# WAirU_v1_1.net
KiCad netlist of a schematic drawn in EAGLE
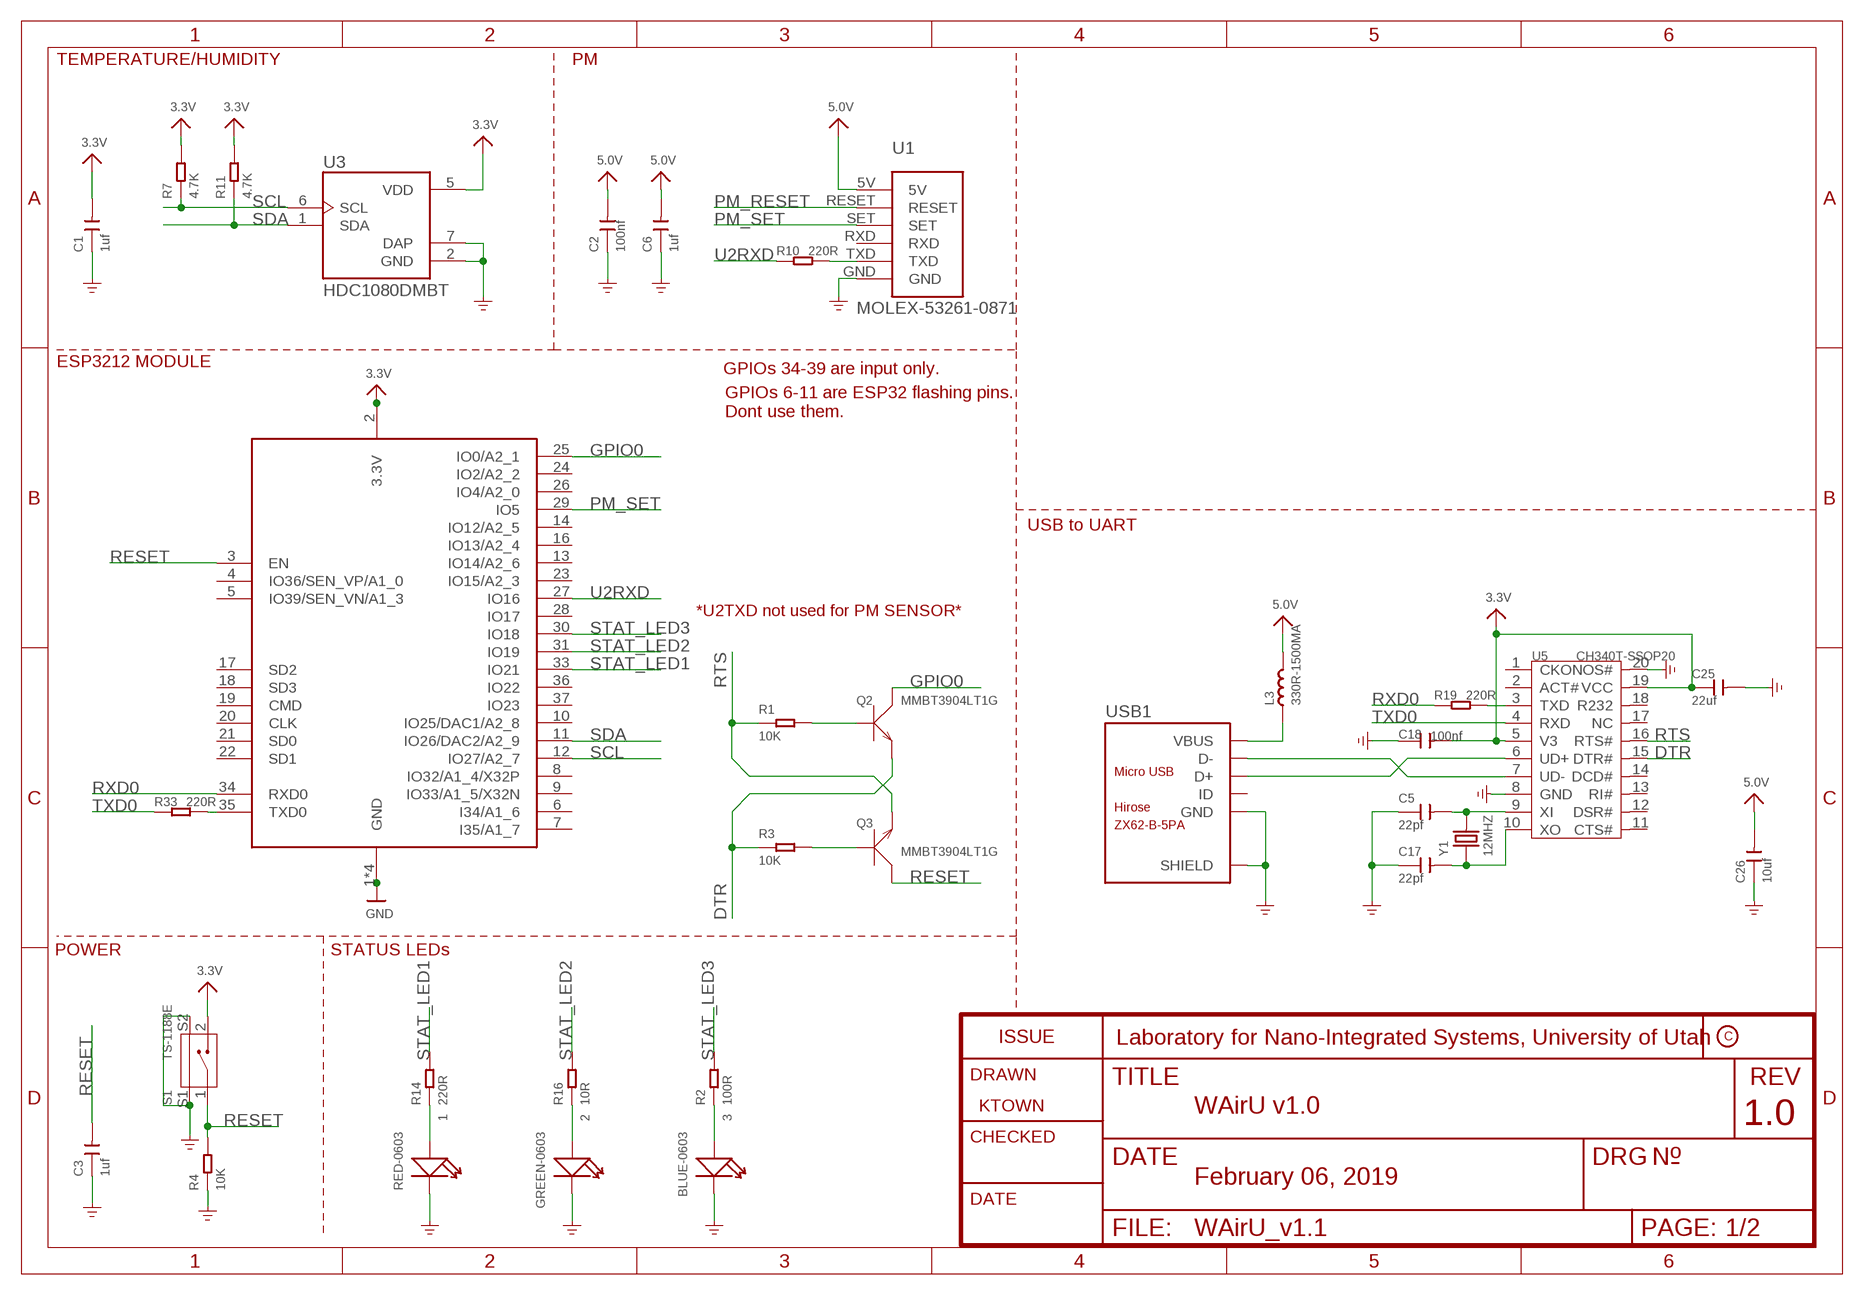
[diagram p0: schematic, sheet 1]
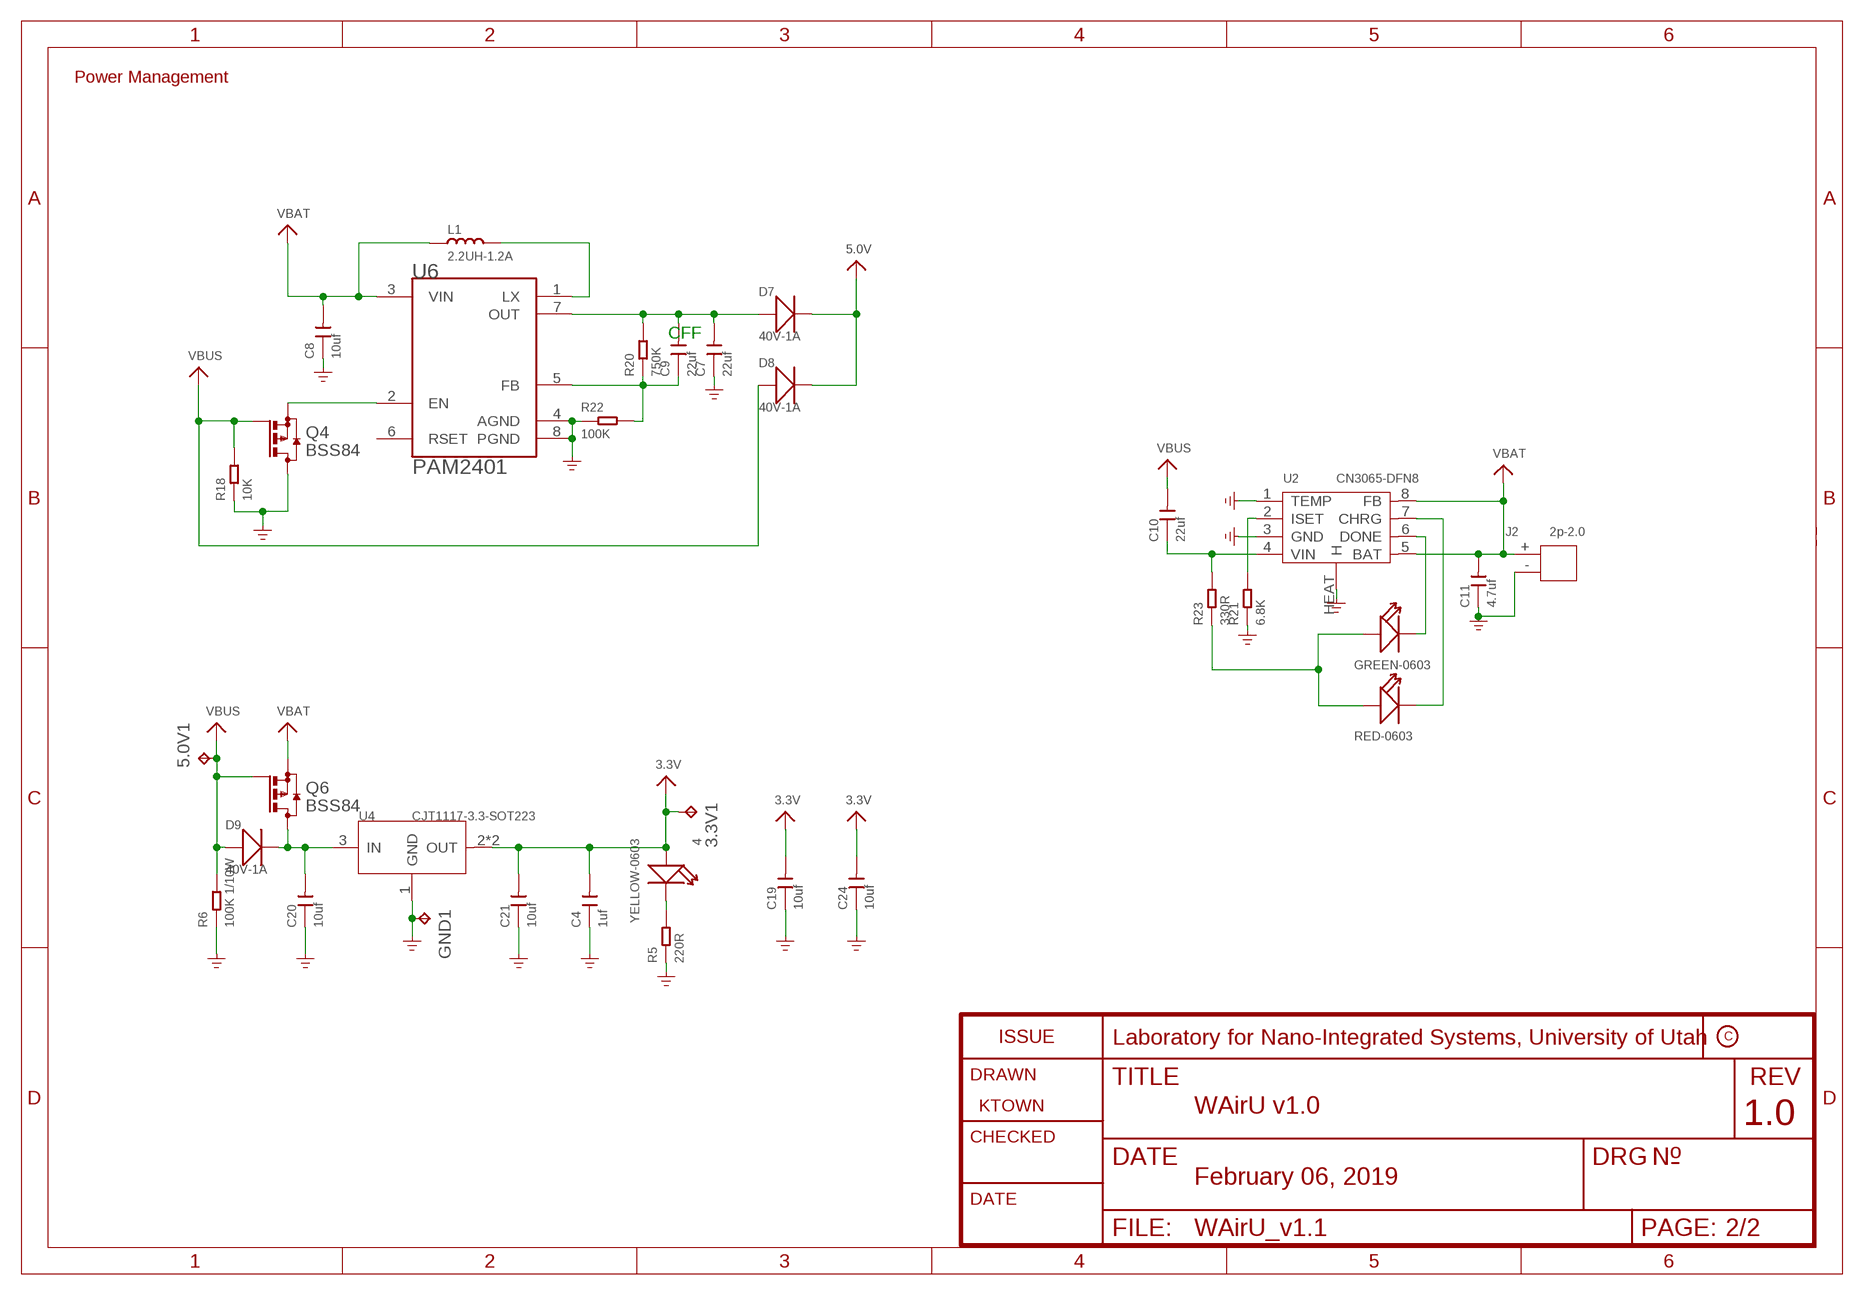
[diagram p1: schematic, sheet 2]

(export (version "E")
  (design (tool "Eeschema 10.0.6"))
  (components
    (comp (ref "1")
      (value "RED-0603")
      (footprint "eagle-import:LED-0603")
      (fields (field (name "MPN") "19-217-R6C-AL1M2VY-3T"))
      (libsource (lib "eagle-import") (part "LED-SMD-RED-DIFFUSED(0603)"))
    )
    (comp (ref "2")
      (value "GREEN-0603")
      (footprint "eagle-import:LED-0603")
      (fields (field (name "MPN") "19-217-G7C-AN1P2-3T"))
      (libsource (lib "eagle-import") (part "SMD-LED-CLEAR-GREEN(0603)"))
    )
    (comp (ref "3")
      (value "BLUE-0603")
      (footprint "eagle-import:LED-0603")
      (fields (field (name "MPN") "19-217-BHC-ZL1M2RY-3T"))
      (libsource (lib "eagle-import") (part "SMD-LED-CLEAR-BLUE(0603)"))
    )
    (comp (ref "C1")
      (value "1uf")
      (footprint "eagle-import:C0603")
      (fields (field (name "MPN") "CC0603KRX7R8BB105"))
      (libsource (lib "eagle-import") (part "CERAMIC-1UF-25V-10%-X7R(0603)"))
    )
    (comp (ref "C2")
      (value "100nf")
      (footprint "eagle-import:C0603")
      (fields (field (name "MPN") "CC0603KRX7R9BB104"))
      (libsource (lib "eagle-import") (part "CERAMIC-100NF-50V-10%-X7R(0603)"))
    )
    (comp (ref "C3")
      (value "1uf")
      (footprint "eagle-import:C0603")
      (fields (field (name "MPN") "CC0603KRX7R8BB105"))
      (libsource (lib "eagle-import") (part "CERAMIC-1UF-25V-10%-X7R(0603)"))
    )
    (comp (ref "C5")
      (value "22pf")
      (footprint "eagle-import:C0603")
      (fields (field (name "MPN") "CC0603JRNPO9BN220"))
      (libsource (lib "eagle-import") (part "CERAMIC-22PF-50V-5%-NPO(0603)"))
    )
    (comp (ref "C6")
      (value "1uf")
      (footprint "eagle-import:C0603")
      (fields (field (name "MPN") "CC0603KRX7R8BB105"))
      (libsource (lib "eagle-import") (part "CERAMIC-1UF-25V-10%-X7R(0603)"))
    )
    (comp (ref "C17")
      (value "22pf")
      (footprint "eagle-import:C0603")
      (fields (field (name "MPN") "CC0603JRNPO9BN220"))
      (libsource (lib "eagle-import") (part "CERAMIC-22PF-50V-5%-NPO(0603)"))
    )
    (comp (ref "C18")
      (value "100nf")
      (footprint "eagle-import:C0603")
      (fields (field (name "MPN") "CC0603KRX7R9BB104"))
      (libsource (lib "eagle-import") (part "CERAMIC-100NF-50V-10%-X7R(0603)"))
    )
    (comp (ref "C25")
      (value "22uf")
      (footprint "eagle-import:C0805")
      (fields (field (name "MPN") "CC0805MKX5R5BB226"))
      (libsource (lib "eagle-import") (part "CERAMIC-22UF-6.3V-20%-X5R(0805)"))
    )
    (comp (ref "C26")
      (value "10uf")
      (footprint "eagle-import:C0603")
      (fields (field (name "MPN") "CC0603KRX5R6BB106"))
      (libsource (lib "eagle-import") (part "Seeed-Capacitor_CERAMIC-10UF-10V-10%-X5R(0603)"))
    )
    (comp (ref "L3")
      (value "330R-1500MA")
      (footprint "eagle-import:L0805")
      (fields (field (name "MPN") "BLM21PG331SN1D"))
      (libsource (lib "eagle-import") (part "SMD-FERRITE-BEAD-330R-1500MA(0805)'0805'"))
    )
    (comp (ref "Q2")
      (value "MMBT3904LT1G")
      (footprint "eagle-import:SOT-23")
      (libsource (lib "eagle-import") (part "SMD-TRANSISTORS-NPN-40V-200MA-MMBT3904LT1G(SOT-23)"))
    )
    (comp (ref "Q3")
      (value "MMBT3904LT1G")
      (footprint "eagle-import:SOT-23")
      (libsource (lib "eagle-import") (part "SMD-TRANSISTORS-NPN-40V-200MA-MMBT3904LT1G(SOT-23)"))
    )
    (comp (ref "R1")
      (value "10K")
      (footprint "eagle-import:R0603")
      (fields (field (name "MPN") "RC0603FR-0710KL"))
      (libsource (lib "eagle-import") (part "SMD-RES-10K-1%-1/10W(0603)"))
    )
    (comp (ref "R2")
      (value "100R")
      (footprint "eagle-import:R0603")
      (fields (field (name "MPN") "RC0603JR-07100RL"))
      (libsource (lib "eagle-import") (part "SMD-RES-100R-5%-1/10W(0603)"))
    )
    (comp (ref "R3")
      (value "10K")
      (footprint "eagle-import:R0603")
      (fields (field (name "MPN") "RC0603FR-0710KL"))
      (libsource (lib "eagle-import") (part "SMD-RES-10K-1%-1/10W(0603)"))
    )
    (comp (ref "R4")
      (value "10K")
      (footprint "eagle-import:R0603")
      (fields (field (name "MPN") "RC0603FR-0710KL"))
      (libsource (lib "eagle-import") (part "SMD-RES-10K-1%-1/10W(0603)"))
    )
    (comp (ref "R7")
      (value "4.7K")
      (footprint "eagle-import:R0603")
      (fields (field (name "MPN") "RC0603JR-074K7L"))
      (libsource (lib "eagle-import") (part "SMD-RES-4.7K-5%-1/10W(0603)"))
    )
    (comp (ref "R10")
      (value "220R")
      (footprint "eagle-import:R0603")
      (fields (field (name "MPN") "RC0603JR-07220RL"))
      (libsource (lib "eagle-import") (part "SMD-RES-220R-5%-1/10W(0603)"))
    )
    (comp (ref "R11")
      (value "4.7K")
      (footprint "eagle-import:R0603")
      (fields (field (name "MPN") "RC0603JR-074K7L"))
      (libsource (lib "eagle-import") (part "SMD-RES-4.7K-5%-1/10W(0603)"))
    )
    (comp (ref "R14")
      (value "220R")
      (footprint "eagle-import:R0603")
      (fields (field (name "MPN") "RC0603JR-07220RL"))
      (libsource (lib "eagle-import") (part "SMD-RES-220R-5%-1/10W(0603)"))
    )
    (comp (ref "R16")
      (value "10R")
      (footprint "eagle-import:R0603")
      (fields (field (name "MPN") "RC0603JR-0710RL"))
      (libsource (lib "eagle-import") (part "SMD-RES-10R-5%-1/10W(0603)"))
    )
    (comp (ref "R19")
      (value "220R")
      (footprint "eagle-import:R0603")
      (fields (field (name "MPN") "RC0603JR-07220RL"))
      (libsource (lib "eagle-import") (part "SMD-RES-220R-5%-1/10W(0603)"))
    )
    (comp (ref "R33")
      (value "220R")
      (footprint "eagle-import:R0603")
      (fields (field (name "MPN") "RC0603JR-07220RL"))
      (libsource (lib "eagle-import") (part "SMD-RES-220R-5%-1/10W(0603)"))
    )
    (comp (ref "S1")
      (value "TS-1188E")
      (footprint "eagle-import:SW4-SMD-7.0X3.5X3.5MM-90D")
      (libsource (lib "eagle-import") (part "SMD-BUTTON(2+2P-7X3.5MM-90D)"))
    )
    (comp (ref "U1")
      (value "MOLEX-53261-0871")
      (footprint "eagle-import:MOLEX-53261-0871")
      (libsource (lib "eagle-import") (part "MOLEX-53261-0871"))
    )
    (comp (ref "U3")
      (value "HDC1080DMBT")
      (footprint "eagle-import:SON100P300X300X80-7N")
      (fields (field (name "DIGI-KEY_PART_NUMBER") "296-43864-1-ND") (field (name "MF") "Texas Instruments"))
      (libsource (lib "eagle-import") (part "HDC1080DMBT"))
    )
    (comp (ref "U5")
      (value "CH340T-SSOP20")
      (footprint "eagle-import:SSOP20-0.65-7.6X5.2MM")
      (fields (field (name "MPN") "CH340T"))
      (libsource (lib "eagle-import") (part "INTERFACE-CH340T(SSOP20)"))
    )
    (comp (ref "U7")
      (value "ESP32_WROOM32_SKINNY")
      (footprint "eagle-import:WROOM32_SKINNY")
      (libsource (lib "eagle-import") (part "ESP32_WROOM32_SKINNY"))
    )
    (comp (ref "USB1")
      (value "ZX62-B-5PA")
      (footprint "eagle-import:MICRO-USB5+6P-SMD-0.65-AB")
      (libsource (lib "eagle-import") (part "MICRO-USB-SMD(ZX62-B-5PA)"))
    )
    (comp (ref "Y1")
      (value "12MHZ")
      (footprint "eagle-import:X2-SMD-5.0X3.2X1.3MM")
      (fields (field (name "MPN") "5032/2P"))
      (libsource (lib "eagle-import") (part "SMD-CRYSTAL-12MHZ-20PF-20PPM-40R(2P-5.0X3.2MM)"))
    )
    (comp (ref "3.3V1")
      (value "TPTP20SQ")
      (footprint "eagle-import:TP20SQ")
      (libsource (lib "eagle-import") (part "TPTP20SQ"))
    )
    (comp (ref "4")
      (value "YELLOW-0603")
      (footprint "eagle-import:LED-0603")
      (fields (field (name "MPN") "19-217-Y5C-AM1N1VY-3T"))
      (libsource (lib "eagle-import") (part "SMD-LED-CLEAR-YELLOW(0603)"))
    )
    (comp (ref "5")
      (value "GREEN-0603")
      (footprint "eagle-import:LED-0603")
      (fields (field (name "MPN") "19-217-G7C-AN1P2-3T"))
      (libsource (lib "eagle-import") (part "SMD-LED-CLEAR-GREEN(0603)"))
    )
    (comp (ref "5.0V1")
      (value "TPTP20SQ")
      (footprint "eagle-import:TP20SQ")
      (libsource (lib "eagle-import") (part "TPTP20SQ"))
    )
    (comp (ref "6")
      (value "RED-0603")
      (footprint "eagle-import:LED-0603")
      (fields (field (name "MPN") "19-217-R6C-AL1M2VY-3T"))
      (libsource (lib "eagle-import") (part "LED-SMD-RED-DIFFUSED(0603)"))
    )
    (comp (ref "C4")
      (value "1uf")
      (footprint "eagle-import:C0603")
      (fields (field (name "MPN") "CC0603KRX7R8BB105"))
      (libsource (lib "eagle-import") (part "CERAMIC-1UF-25V-10%-X7R(0603)"))
    )
    (comp (ref "C7")
      (value "22uf")
      (footprint "eagle-import:C0603")
      (fields (field (name "MPN") "CC0603KRX5R6BB106"))
      (libsource (lib "eagle-import") (part "CERAMIC-10UF-10V-10%-X5R(0603)"))
    )
    (comp (ref "C8")
      (value "10uf")
      (footprint "eagle-import:C0603")
      (fields (field (name "MPN") "CC0603KRX5R6BB106"))
      (libsource (lib "eagle-import") (part "CERAMIC-10UF-10V-10%-X5R(0603)"))
    )
    (comp (ref "C9")
      (value "22uf")
      (footprint "eagle-import:C0603")
      (fields (field (name "MPN") "CC0603KRX5R6BB106"))
      (libsource (lib "eagle-import") (part "CERAMIC-10UF-10V-10%-X5R(0603)"))
    )
    (comp (ref "C10")
      (value "22uf")
      (footprint "eagle-import:C0603")
      (fields (field (name "MPN") "CC0603KRX5R6BB106"))
      (libsource (lib "eagle-import") (part "CERAMIC-10UF-10V-10%-X5R(0603)"))
    )
    (comp (ref "C11")
      (value "4.7uf")
      (footprint "eagle-import:C0603")
      (fields (field (name "MPN") "CC0603KRX5R6BB475"))
      (libsource (lib "eagle-import") (part "CERAMIC-4.7UF-10V-10%-X5R(0603)"))
    )
    (comp (ref "C19")
      (value "10uf")
      (footprint "eagle-import:C0603")
      (fields (field (name "MPN") "CC0603KRX5R6BB106"))
      (libsource (lib "eagle-import") (part "Seeed-Capacitor_CERAMIC-10UF-10V-10%-X5R(0603)"))
    )
    (comp (ref "C20")
      (value "10uf")
      (footprint "eagle-import:C0603")
      (fields (field (name "MPN") "CC0603KRX5R6BB106"))
      (libsource (lib "eagle-import") (part "Seeed-Capacitor_CERAMIC-10UF-10V-10%-X5R(0603)"))
    )
    (comp (ref "C21")
      (value "10uf")
      (footprint "eagle-import:C0603")
      (fields (field (name "MPN") "CC0603KRX5R6BB106"))
      (libsource (lib "eagle-import") (part "Seeed-Capacitor_CERAMIC-10UF-10V-10%-X5R(0603)"))
    )
    (comp (ref "C24")
      (value "10uf")
      (footprint "eagle-import:C0603")
      (fields (field (name "MPN") "CC0603KRX5R6BB106"))
      (libsource (lib "eagle-import") (part "Seeed-Capacitor_CERAMIC-10UF-10V-10%-X5R(0603)"))
    )
    (comp (ref "D7")
      (value "40V-1A")
      (footprint "eagle-import:DO-214AC")
      (fields (field (name "MPN") "1N5819"))
      (libsource (lib "eagle-import") (part "SMD-DIODE-SCHOTTKY-40V-1A(DO-214AC)"))
    )
    (comp (ref "D8")
      (value "40V-1A")
      (footprint "eagle-import:DO-214AC")
      (fields (field (name "MPN") "1N5819"))
      (libsource (lib "eagle-import") (part "SMD-DIODE-SCHOTTKY-40V-1A(DO-214AC)"))
    )
    (comp (ref "D9")
      (value "40V-1A")
      (footprint "eagle-import:DO-214AC")
      (fields (field (name "MPN") "1N5819"))
      (libsource (lib "eagle-import") (part "SMD-DIODE-SCHOTTKY-40V-1A(DO-214AC)"))
    )
    (comp (ref "GND1")
      (value "TPTP20SQ")
      (footprint "eagle-import:TP20SQ")
      (libsource (lib "eagle-import") (part "TPTP20SQ"))
    )
    (comp (ref "J2")
      (value "2p-2.0")
      (footprint "eagle-import:H2-2.0-6X4.5MM")
      (libsource (lib "eagle-import") (part "DIP-JST-2P-2.0"))
    )
    (comp (ref "L1")
      (value "2.2UH-1.2A")
      (footprint "eagle-import:L0805")
      (fields (field (name "MPN") "LQM2MPN2R2MG0"))
      (libsource (lib "eagle-import") (part "SMD-INDUCTOR-2.2UH-20%-1.2A(0805)"))
    )
    (comp (ref "Q4")
      (value "BSS84")
      (footprint "eagle-import:SOT23")
      (fields (field (name "MF") "MICROSS/On Semiconductor"))
      (libsource (lib "eagle-import") (part "BSS84"))
    )
    (comp (ref "Q6")
      (value "BSS84")
      (footprint "eagle-import:SOT23")
      (fields (field (name "MF") "MICROSS/On Semiconductor"))
      (libsource (lib "eagle-import") (part "BSS84"))
    )
    (comp (ref "R5")
      (value "220R")
      (footprint "eagle-import:R0603")
      (fields (field (name "MPN") "RC0603JR-07220RL"))
      (libsource (lib "eagle-import") (part "SMD-RES-220R-5%-1/10W(0603)"))
    )
    (comp (ref "R6")
      (value "100K 1/10W")
      (footprint "eagle-import:R0603")
      (fields (field (name "MPN") "RC0603JR-07100KL"))
      (libsource (lib "eagle-import") (part "Seeed-Resistor_SMD-RES-100K-5%-1/10W(0603)"))
    )
    (comp (ref "R18")
      (value "10K")
      (footprint "eagle-import:R0603")
      (fields (field (name "MPN") "RC0603FR-0710KL"))
      (libsource (lib "eagle-import") (part "SMD-RES-10K-1%-1/10W(0603)"))
    )
    (comp (ref "R20")
      (value "750K")
      (footprint "eagle-import:R0603")
      (fields (field (name "MPN") "RC0603JR-07100KL"))
      (libsource (lib "eagle-import") (part "SMD-RES-100K-5%-1/10W(0603)"))
    )
    (comp (ref "R21")
      (value "6.8K")
      (footprint "eagle-import:R0603")
      (fields (field (name "MPN") "RC0805JR-07220KL"))
      (libsource (lib "eagle-import") (part "SMD-RES-6.8K-1%-1/10W(0603)"))
    )
    (comp (ref "R22")
      (value "100K")
      (footprint "eagle-import:R0603")
      (fields (field (name "MPN") "RC0603JR-07100KL"))
      (libsource (lib "eagle-import") (part "SMD-RES-100K-5%-1/10W(0603)"))
    )
    (comp (ref "R23")
      (value "330R")
      (footprint "eagle-import:R0603")
      (fields (field (name "MPN") "RC0603FR-07330RL"))
      (libsource (lib "eagle-import") (part "SMD-RES-330R-1%-1/10W(0603)"))
    )
    (comp (ref "U2")
      (value "CN3065-DFN8")
      (footprint "eagle-import:DFN8G-0.5-3X3MM")
      (fields (field (name "MPN") "CN3065"))
      (libsource (lib "eagle-import") (part "PMIC-CN3065(DFN8)"))
    )
    (comp (ref "U4")
      (value "CJT1117-3.3-SOT223")
      (footprint "eagle-import:SOT-223")
      (fields (field (name "MPN") "CJT1117-3.3"))
      (libsource (lib "eagle-import") (part "PMIC-CJT1117-3.3(SOT223)"))
    )
    (comp (ref "U6")
      (value "PAM2401")
      (footprint "eagle-import:MSOP-8")
      (libsource (lib "eagle-import") (part "PAM2401"))
    )
  )
  (nets
    (net (code "1") (name "3.3V") (class "Default")
      (node (ref "3.3V1") (pin "TP") (pinfunction "TP_TP") (pintype "input"))
      (node (ref "4") (pin "+") (pinfunction "+_+") (pintype "passive"))
      (node (ref "C1") (pin "2") (pinfunction "2_2") (pintype "passive"))
      (node (ref "C18") (pin "2") (pinfunction "2_2") (pintype "passive"))
      (node (ref "C19") (pin "2") (pinfunction "2_2") (pintype "passive"))
      (node (ref "C21") (pin "2") (pinfunction "2_2") (pintype "passive"))
      (node (ref "C24") (pin "2") (pinfunction "2_2") (pintype "passive"))
      (node (ref "C25") (pin "1") (pinfunction "1_1") (pintype "passive"))
      (node (ref "C4") (pin "2") (pinfunction "2_2") (pintype "passive"))
      (node (ref "R11") (pin "2") (pinfunction "2_2") (pintype "passive"))
      (node (ref "R7") (pin "2") (pinfunction "2_2") (pintype "passive"))
      (node (ref "S1") (pin "2") (pinfunction "2_2") (pintype "bidirectional"))
      (node (ref "U3") (pin "5") (pinfunction "VDD_5") (pintype "power_in"))
      (node (ref "U4") (pin "2") (pinfunction "OUT_2") (pintype "bidirectional"))
      (node (ref "U4") (pin "TER") (pinfunction "OUT_TER") (pintype "bidirectional"))
      (node (ref "U5") (pin "19") (pinfunction "VCC_19") (pintype "power_in"))
      (node (ref "U5") (pin "5") (pinfunction "V3_5") (pintype "power_in"))
      (node (ref "U7") (pin "2") (pinfunction "3.3V_2") (pintype "passive"))
    )
    (net (code "2") (name "5.0V") (class "Default")
      (node (ref "C2") (pin "2") (pinfunction "2_2") (pintype "passive"))
      (node (ref "C26") (pin "2") (pinfunction "2_2") (pintype "passive"))
      (node (ref "C6") (pin "2") (pinfunction "2_2") (pintype "passive"))
      (node (ref "D7") (pin "2") (pinfunction "-_2") (pintype "passive"))
      (node (ref "D8") (pin "2") (pinfunction "-_2") (pintype "passive"))
      (node (ref "L3") (pin "2") (pinfunction "2_2") (pintype "passive"))
      (node (ref "U1") (pin "5V") (pinfunction "5V_5V") (pintype "bidirectional"))
    )
    (net (code "3") (name "DTR") (class "Default")
      (node (ref "Q2") (pin "2") (pinfunction "E_2") (pintype "passive"))
      (node (ref "R3") (pin "1") (pinfunction "1_1") (pintype "passive"))
      (node (ref "U5") (pin "15") (pinfunction "DTR#_15") (pintype "output"))
    )
    (net (code "4") (name "GND") (class "Default")
      (node (ref "1") (pin "-") (pinfunction "-_-") (pintype "passive"))
      (node (ref "2") (pin "-") (pinfunction "-_-") (pintype "passive"))
      (node (ref "3") (pin "-") (pinfunction "-_-") (pintype "passive"))
      (node (ref "C1") (pin "1") (pinfunction "1_1") (pintype "passive"))
      (node (ref "C11") (pin "1") (pinfunction "1_1") (pintype "passive"))
      (node (ref "C17") (pin "1") (pinfunction "1_1") (pintype "passive"))
      (node (ref "C18") (pin "1") (pinfunction "1_1") (pintype "passive"))
      (node (ref "C19") (pin "1") (pinfunction "1_1") (pintype "passive"))
      (node (ref "C2") (pin "1") (pinfunction "1_1") (pintype "passive"))
      (node (ref "C20") (pin "1") (pinfunction "1_1") (pintype "passive"))
      (node (ref "C21") (pin "1") (pinfunction "1_1") (pintype "passive"))
      (node (ref "C24") (pin "1") (pinfunction "1_1") (pintype "passive"))
      (node (ref "C25") (pin "2") (pinfunction "2_2") (pintype "passive"))
      (node (ref "C26") (pin "1") (pinfunction "1_1") (pintype "passive"))
      (node (ref "C3") (pin "1") (pinfunction "1_1") (pintype "passive"))
      (node (ref "C4") (pin "1") (pinfunction "1_1") (pintype "passive"))
      (node (ref "C5") (pin "1") (pinfunction "1_1") (pintype "passive"))
      (node (ref "C6") (pin "1") (pinfunction "1_1") (pintype "passive"))
      (node (ref "C7") (pin "1") (pinfunction "1_1") (pintype "passive"))
      (node (ref "C8") (pin "1") (pinfunction "1_1") (pintype "passive"))
      (node (ref "GND1") (pin "TP") (pinfunction "TP_TP") (pintype "input"))
      (node (ref "J2") (pin "-") (pinfunction "P$2_-") (pintype "bidirectional"))
      (node (ref "Q4") (pin "3") (pinfunction "D_3") (pintype "passive"))
      (node (ref "R18") (pin "1") (pinfunction "1_1") (pintype "passive"))
      (node (ref "R21") (pin "1") (pinfunction "1_1") (pintype "passive"))
      (node (ref "R22") (pin "1") (pinfunction "1_1") (pintype "passive"))
      (node (ref "R4") (pin "1") (pinfunction "1_1") (pintype "passive"))
      (node (ref "R5") (pin "1") (pinfunction "1_1") (pintype "passive"))
      (node (ref "R6") (pin "1") (pinfunction "1_1") (pintype "passive"))
      (node (ref "S1") (pin "S1") (pinfunction "S1_S1") (pintype "bidirectional"))
      (node (ref "S1") (pin "S2") (pinfunction "S2_S2") (pintype "bidirectional"))
      (node (ref "U1") (pin "GND") (pinfunction "GND_GND") (pintype "bidirectional"))
      (node (ref "U2") (pin "1") (pinfunction "TEMP_1") (pintype "input"))
      (node (ref "U2") (pin "3") (pinfunction "GND_3") (pintype "power_in"))
      (node (ref "U2") (pin "HEAT") (pinfunction "H_HEAT") (pintype "bidirectional"))
      (node (ref "U3") (pin "2") (pinfunction "GND_2") (pintype "power_in"))
      (node (ref "U3") (pin "7") (pinfunction "DAP_7") (pintype "power_in"))
      (node (ref "U4") (pin "1") (pinfunction "GND_1") (pintype "bidirectional"))
      (node (ref "U5") (pin "20") (pinfunction "NOS#_20") (pintype "power_in"))
      (node (ref "U5") (pin "8") (pinfunction "GND_8") (pintype "power_in"))
      (node (ref "U6") (pin "4") (pinfunction "AGND_4") (pintype "bidirectional"))
      (node (ref "U6") (pin "8") (pinfunction "PGND_8") (pintype "bidirectional"))
      (node (ref "U7") (pin "1") (pinfunction "GND_1") (pintype "passive"))
      (node (ref "U7") (pin "15") (pinfunction "GND_15") (pintype "passive"))
      (node (ref "U7") (pin "38") (pinfunction "GND_38") (pintype "passive"))
      (node (ref "U7") (pin "P$1") (pinfunction "GND_P$1") (pintype "passive"))
      (node (ref "USB1") (pin "5") (pinfunction "GND_5") (pintype "power_in"))
      (node (ref "USB1") (pin "P1") (pinfunction "SHIELD_P1") (pintype "power_in"))
      (node (ref "USB1") (pin "P2") (pinfunction "SHIELD_P2") (pintype "power_in"))
      (node (ref "USB1") (pin "P3_1") (pinfunction "SHIELD_P3_1") (pintype "power_in"))
      (node (ref "USB1") (pin "P3_2") (pinfunction "SHIELD_P3_2") (pintype "power_in"))
      (node (ref "USB1") (pin "P3_3") (pinfunction "SHIELD_P3_3") (pintype "power_in"))
      (node (ref "USB1") (pin "P4_1") (pinfunction "SHIELD_P4_1") (pintype "power_in"))
      (node (ref "USB1") (pin "P4_2") (pinfunction "SHIELD_P4_2") (pintype "power_in"))
      (node (ref "USB1") (pin "P4_3") (pinfunction "SHIELD_P4_3") (pintype "power_in"))
      (node (ref "USB1") (pin "P5") (pinfunction "SHIELD_P5") (pintype "power_in"))
      (node (ref "USB1") (pin "P6") (pinfunction "SHIELD_P6") (pintype "power_in"))
    )
    (net (code "5") (name "GPIO0") (class "Default")
      (node (ref "Q2") (pin "3") (pinfunction "C_3") (pintype "passive"))
      (node (ref "U7") (pin "25") (pinfunction "IO0/A2_1_25") (pintype "bidirectional"))
    )
    (net (code "6") (name "Net-(1-Pad+)") (class "Default")
      (node (ref "1") (pin "+") (pinfunction "+_+") (pintype "passive"))
      (node (ref "R14") (pin "1") (pinfunction "1_1") (pintype "passive"))
    )
    (net (code "7") (name "Net-(2-Pad+)") (class "Default")
      (node (ref "2") (pin "+") (pinfunction "+_+") (pintype "passive"))
      (node (ref "R16") (pin "1") (pinfunction "1_1") (pintype "passive"))
    )
    (net (code "8") (name "Net-(3-Pad+)") (class "Default")
      (node (ref "3") (pin "+") (pinfunction "+_+") (pintype "passive"))
      (node (ref "R2") (pin "1") (pinfunction "1_1") (pintype "passive"))
    )
    (net (code "9") (name "Net-(4-Pad-)") (class "Default")
      (node (ref "4") (pin "-") (pinfunction "-_-") (pintype "passive"))
      (node (ref "R5") (pin "2") (pinfunction "2_2") (pintype "passive"))
    )
    (net (code "10") (name "Net-(5-Pad+)") (class "Default")
      (node (ref "5") (pin "+") (pinfunction "+_+") (pintype "passive"))
      (node (ref "6") (pin "+") (pinfunction "+_+") (pintype "passive"))
      (node (ref "R23") (pin "1") (pinfunction "1_1") (pintype "passive"))
    )
    (net (code "11") (name "Net-(D7-+)") (class "Default")
      (node (ref "C7") (pin "2") (pinfunction "2_2") (pintype "passive"))
      (node (ref "C9") (pin "2") (pinfunction "2_2") (pintype "passive"))
      (node (ref "D7") (pin "1") (pinfunction "+_1") (pintype "passive"))
      (node (ref "R20") (pin "2") (pinfunction "2_2") (pintype "passive"))
      (node (ref "U6") (pin "7") (pinfunction "OUT_7") (pintype "bidirectional"))
    )
    (net (code "12") (name "Net-(D9--)") (class "Default")
      (node (ref "C20") (pin "2") (pinfunction "2_2") (pintype "passive"))
      (node (ref "D9") (pin "2") (pinfunction "-_2") (pintype "passive"))
      (node (ref "Q6") (pin "3") (pinfunction "D_3") (pintype "passive"))
      (node (ref "U4") (pin "3") (pinfunction "IN_3") (pintype "bidirectional"))
    )
    (net (code "13") (name "Net-(Q2-B)") (class "Default")
      (node (ref "Q2") (pin "1") (pinfunction "B_1") (pintype "passive"))
      (node (ref "R1") (pin "2") (pinfunction "2_2") (pintype "passive"))
    )
    (net (code "14") (name "Net-(Q3-B)") (class "Default")
      (node (ref "Q3") (pin "1") (pinfunction "B_1") (pintype "passive"))
      (node (ref "R3") (pin "2") (pinfunction "2_2") (pintype "passive"))
    )
    (net (code "15") (name "Net-(Q4-S)") (class "Default")
      (node (ref "Q4") (pin "2") (pinfunction "S_2") (pintype "passive"))
      (node (ref "U6") (pin "2") (pinfunction "EN_2") (pintype "bidirectional"))
    )
    (net (code "16") (name "Net-(R10-Pad2)") (class "Default")
      (node (ref "R10") (pin "2") (pinfunction "2_2") (pintype "passive"))
      (node (ref "U1") (pin "TXD") (pinfunction "TXD_TXD") (pintype "bidirectional"))
    )
    (net (code "17") (name "Net-(U2-CHRG)") (class "Default")
      (node (ref "6") (pin "-") (pinfunction "-_-") (pintype "passive"))
      (node (ref "U2") (pin "7") (pinfunction "CHRG_7") (pintype "bidirectional"))
    )
    (net (code "18") (name "Net-(U2-DONE)") (class "Default")
      (node (ref "5") (pin "-") (pinfunction "-_-") (pintype "passive"))
      (node (ref "U2") (pin "6") (pinfunction "DONE_6") (pintype "bidirectional"))
    )
    (net (code "19") (name "Net-(U2-ISET)") (class "Default")
      (node (ref "R21") (pin "2") (pinfunction "2_2") (pintype "passive"))
      (node (ref "U2") (pin "2") (pinfunction "ISET_2") (pintype "bidirectional"))
    )
    (net (code "20") (name "Net-(U2-VIN)") (class "Default")
      (node (ref "C10") (pin "1") (pinfunction "1_1") (pintype "passive"))
      (node (ref "R23") (pin "2") (pinfunction "2_2") (pintype "passive"))
      (node (ref "U2") (pin "4") (pinfunction "VIN_4") (pintype "input"))
    )
    (net (code "21") (name "Net-(U5-TXD)") (class "Default")
      (node (ref "R19") (pin "2") (pinfunction "2_2") (pintype "passive"))
      (node (ref "U5") (pin "3") (pinfunction "TXD_3") (pintype "output"))
    )
    (net (code "22") (name "Net-(U5-UD+)") (class "Default")
      (node (ref "U5") (pin "6") (pinfunction "UD+_6") (pintype "bidirectional"))
      (node (ref "USB1") (pin "3") (pinfunction "D+_3") (pintype "bidirectional"))
    )
    (net (code "23") (name "Net-(U5-UD-)") (class "Default")
      (node (ref "U5") (pin "7") (pinfunction "UD-_7") (pintype "bidirectional"))
      (node (ref "USB1") (pin "2") (pinfunction "D-_2") (pintype "bidirectional"))
    )
    (net (code "24") (name "Net-(U5-XI)") (class "Default")
      (node (ref "C5") (pin "2") (pinfunction "2_2") (pintype "passive"))
      (node (ref "U5") (pin "9") (pinfunction "XI_9") (pintype "input"))
      (node (ref "Y1") (pin "2") (pinfunction "2_2") (pintype "passive"))
    )
    (net (code "25") (name "Net-(U5-XO)") (class "Default")
      (node (ref "C17") (pin "2") (pinfunction "2_2") (pintype "passive"))
      (node (ref "U5") (pin "10") (pinfunction "XO_10") (pintype "output"))
      (node (ref "Y1") (pin "1") (pinfunction "1_1") (pintype "passive"))
    )
    (net (code "26") (name "Net-(U6-FB)") (class "Default")
      (node (ref "C9") (pin "1") (pinfunction "1_1") (pintype "passive"))
      (node (ref "R20") (pin "1") (pinfunction "1_1") (pintype "passive"))
      (node (ref "R22") (pin "2") (pinfunction "2_2") (pintype "passive"))
      (node (ref "U6") (pin "5") (pinfunction "FB_5") (pintype "bidirectional"))
    )
    (net (code "27") (name "Net-(U6-LX)") (class "Default")
      (node (ref "L1") (pin "2") (pinfunction "2_2") (pintype "passive"))
      (node (ref "U6") (pin "1") (pinfunction "LX_1") (pintype "bidirectional"))
    )
    (net (code "28") (name "Net-(U7-TXD0)") (class "Default")
      (node (ref "R33") (pin "2") (pinfunction "2_2") (pintype "passive"))
      (node (ref "U7") (pin "35") (pinfunction "TXD0_35") (pintype "output"))
    )
    (net (code "29") (name "PM_RESET") (class "Default")
      (node (ref "U1") (pin "RESET") (pinfunction "RESET_RESET") (pintype "bidirectional"))
    )
    (net (code "30") (name "PM_SET") (class "Default")
      (node (ref "U1") (pin "SET") (pinfunction "SET_SET") (pintype "bidirectional"))
      (node (ref "U7") (pin "29") (pinfunction "IO5_29") (pintype "bidirectional"))
    )
    (net (code "31") (name "RESET") (class "Default")
      (node (ref "C3") (pin "2") (pinfunction "2_2") (pintype "passive"))
      (node (ref "Q3") (pin "3") (pinfunction "C_3") (pintype "passive"))
      (node (ref "R4") (pin "2") (pinfunction "2_2") (pintype "passive"))
      (node (ref "S1") (pin "1") (pinfunction "1_1") (pintype "bidirectional"))
      (node (ref "U7") (pin "3") (pinfunction "EN_3") (pintype "input"))
    )
    (net (code "32") (name "RTS") (class "Default")
      (node (ref "Q3") (pin "2") (pinfunction "E_2") (pintype "passive"))
      (node (ref "R1") (pin "1") (pinfunction "1_1") (pintype "passive"))
      (node (ref "U5") (pin "16") (pinfunction "RTS#_16") (pintype "output"))
    )
    (net (code "33") (name "RXD0") (class "Default")
      (node (ref "R19") (pin "1") (pinfunction "1_1") (pintype "passive"))
      (node (ref "U7") (pin "34") (pinfunction "RXD0_34") (pintype "input"))
    )
    (net (code "34") (name "SCL") (class "Default")
      (node (ref "R7") (pin "1") (pinfunction "1_1") (pintype "passive"))
      (node (ref "U3") (pin "6") (pinfunction "SCL_6") (pintype "input"))
      (node (ref "U7") (pin "12") (pinfunction "IO27/A2_7_12") (pintype "bidirectional"))
    )
    (net (code "35") (name "SDA") (class "Default")
      (node (ref "R11") (pin "1") (pinfunction "1_1") (pintype "passive"))
      (node (ref "U3") (pin "1") (pinfunction "SDA_1") (pintype "bidirectional"))
      (node (ref "U7") (pin "11") (pinfunction "IO26/DAC2/A2_9_11") (pintype "bidirectional"))
    )
    (net (code "36") (name "STAT_LED1") (class "Default")
      (node (ref "R14") (pin "2") (pinfunction "2_2") (pintype "passive"))
      (node (ref "U7") (pin "33") (pinfunction "IO21_33") (pintype "bidirectional"))
    )
    (net (code "37") (name "STAT_LED2") (class "Default")
      (node (ref "R16") (pin "2") (pinfunction "2_2") (pintype "passive"))
      (node (ref "U7") (pin "31") (pinfunction "IO19_31") (pintype "bidirectional"))
    )
    (net (code "38") (name "STAT_LED3") (class "Default")
      (node (ref "R2") (pin "2") (pinfunction "2_2") (pintype "passive"))
      (node (ref "U7") (pin "30") (pinfunction "IO18_30") (pintype "bidirectional"))
    )
    (net (code "39") (name "TXD0") (class "Default")
      (node (ref "R33") (pin "1") (pinfunction "1_1") (pintype "passive"))
      (node (ref "U5") (pin "4") (pinfunction "RXD_4") (pintype "input"))
    )
    (net (code "40") (name "U2RXD") (class "Default")
      (node (ref "R10") (pin "1") (pinfunction "1_1") (pintype "passive"))
      (node (ref "U7") (pin "27") (pinfunction "IO16_27") (pintype "bidirectional"))
    )
    (net (code "41") (name "VBAT") (class "Default")
      (node (ref "C11") (pin "2") (pinfunction "2_2") (pintype "passive"))
      (node (ref "C8") (pin "2") (pinfunction "2_2") (pintype "passive"))
      (node (ref "J2") (pin "+") (pinfunction "P$1_+") (pintype "bidirectional"))
      (node (ref "L1") (pin "1") (pinfunction "1_1") (pintype "passive"))
      (node (ref "Q6") (pin "2") (pinfunction "S_2") (pintype "passive"))
      (node (ref "U2") (pin "5") (pinfunction "BAT_5") (pintype "bidirectional"))
      (node (ref "U2") (pin "8") (pinfunction "FB_8") (pintype "input"))
      (node (ref "U6") (pin "3") (pinfunction "VIN_3") (pintype "bidirectional"))
    )
    (net (code "42") (name "VBUS") (class "Default")
      (node (ref "5.0V1") (pin "TP") (pinfunction "TP_TP") (pintype "input"))
      (node (ref "C10") (pin "2") (pinfunction "2_2") (pintype "passive"))
      (node (ref "D8") (pin "1") (pinfunction "+_1") (pintype "passive"))
      (node (ref "D9") (pin "1") (pinfunction "+_1") (pintype "passive"))
      (node (ref "L3") (pin "1") (pinfunction "1_1") (pintype "passive"))
      (node (ref "Q4") (pin "1") (pinfunction "G_1") (pintype "passive"))
      (node (ref "Q6") (pin "1") (pinfunction "G_1") (pintype "passive"))
      (node (ref "R18") (pin "2") (pinfunction "2_2") (pintype "passive"))
      (node (ref "R6") (pin "2") (pinfunction "2_2") (pintype "passive"))
      (node (ref "USB1") (pin "1") (pinfunction "VBUS_1") (pintype "power_in"))
    )
    (net (code "43") (name "unconnected-(U1-PadRXD)") (class "Default")
      (node (ref "U1") (pin "RXD") (pinfunction "RXD_RXD") (pintype "bidirectional"))
    )
    (net (code "44") (name "unconnected-(U5-ACT#-Pad2)") (class "Default")
      (node (ref "U5") (pin "2") (pinfunction "ACT#_2") (pintype "output"))
    )
    (net (code "45") (name "unconnected-(U5-CKO-Pad1)") (class "Default")
      (node (ref "U5") (pin "1") (pinfunction "CKO_1") (pintype "output"))
    )
    (net (code "46") (name "unconnected-(U5-CTS#-Pad11)") (class "Default")
      (node (ref "U5") (pin "11") (pinfunction "CTS#_11") (pintype "input"))
    )
    (net (code "47") (name "unconnected-(U5-DCD#-Pad14)") (class "Default")
      (node (ref "U5") (pin "14") (pinfunction "DCD#_14") (pintype "input"))
    )
    (net (code "48") (name "unconnected-(U5-DSR#-Pad12)") (class "Default")
      (node (ref "U5") (pin "12") (pinfunction "DSR#_12") (pintype "input"))
    )
    (net (code "49") (name "unconnected-(U5-NC-Pad17)") (class "Default")
      (node (ref "U5") (pin "17") (pinfunction "NC_17") (pintype "no_connect"))
    )
    (net (code "50") (name "unconnected-(U5-R232-Pad18)") (class "Default")
      (node (ref "U5") (pin "18") (pinfunction "R232_18") (pintype "input"))
    )
    (net (code "51") (name "unconnected-(U5-RI#-Pad13)") (class "Default")
      (node (ref "U5") (pin "13") (pinfunction "RI#_13") (pintype "input"))
    )
    (net (code "52") (name "unconnected-(U6-RSET-Pad6)") (class "Default")
      (node (ref "U6") (pin "6") (pinfunction "RSET_6") (pintype "bidirectional"))
    )
    (net (code "53") (name "unconnected-(U7-CLK-Pad20)") (class "Default")
      (node (ref "U7") (pin "20") (pinfunction "CLK_20") (pintype "bidirectional"))
    )
    (net (code "54") (name "unconnected-(U7-CMD-Pad19)") (class "Default")
      (node (ref "U7") (pin "19") (pinfunction "CMD_19") (pintype "bidirectional"))
    )
    (net (code "55") (name "unconnected-(U7-I34{slash}A1_6-Pad6)") (class "Default")
      (node (ref "U7") (pin "6") (pinfunction "I34/A1_6_6") (pintype "bidirectional"))
    )
    (net (code "56") (name "unconnected-(U7-I35{slash}A1_7-Pad7)") (class "Default")
      (node (ref "U7") (pin "7") (pinfunction "I35/A1_7_7") (pintype "bidirectional"))
    )
    (net (code "57") (name "unconnected-(U7-IO2{slash}A2_2-Pad24)") (class "Default")
      (node (ref "U7") (pin "24") (pinfunction "IO2/A2_2_24") (pintype "bidirectional"))
    )
    (net (code "58") (name "unconnected-(U7-IO4{slash}A2_0-Pad26)") (class "Default")
      (node (ref "U7") (pin "26") (pinfunction "IO4/A2_0_26") (pintype "bidirectional"))
    )
    (net (code "59") (name "unconnected-(U7-IO12{slash}A2_5-Pad14)") (class "Default")
      (node (ref "U7") (pin "14") (pinfunction "IO12/A2_5_14") (pintype "bidirectional"))
    )
    (net (code "60") (name "unconnected-(U7-IO13{slash}A2_4-Pad16)") (class "Default")
      (node (ref "U7") (pin "16") (pinfunction "IO13/A2_4_16") (pintype "bidirectional"))
    )
    (net (code "61") (name "unconnected-(U7-IO14{slash}A2_6-Pad13)") (class "Default")
      (node (ref "U7") (pin "13") (pinfunction "IO14/A2_6_13") (pintype "bidirectional"))
    )
    (net (code "62") (name "unconnected-(U7-IO15{slash}A2_3-Pad23)") (class "Default")
      (node (ref "U7") (pin "23") (pinfunction "IO15/A2_3_23") (pintype "bidirectional"))
    )
    (net (code "63") (name "unconnected-(U7-IO17-Pad28)") (class "Default")
      (node (ref "U7") (pin "28") (pinfunction "IO17_28") (pintype "bidirectional"))
    )
    (net (code "64") (name "unconnected-(U7-IO22-Pad36)") (class "Default")
      (node (ref "U7") (pin "36") (pinfunction "IO22_36") (pintype "bidirectional"))
    )
    (net (code "65") (name "unconnected-(U7-IO23-Pad37)") (class "Default")
      (node (ref "U7") (pin "37") (pinfunction "IO23_37") (pintype "bidirectional"))
    )
    (net (code "66") (name "unconnected-(U7-IO25{slash}DAC1{slash}A2_8-Pad10)") (class "Default")
      (node (ref "U7") (pin "10") (pinfunction "IO25/DAC1/A2_8_10") (pintype "bidirectional"))
    )
    (net (code "67") (name "unconnected-(U7-IO32{slash}A1_4{slash}X32P-Pad8)") (class "Default")
      (node (ref "U7") (pin "8") (pinfunction "IO32/A1_4/X32P_8") (pintype "bidirectional"))
    )
    (net (code "68") (name "unconnected-(U7-IO33{slash}A1_5{slash}X32N-Pad9)") (class "Default")
      (node (ref "U7") (pin "9") (pinfunction "IO33/A1_5/X32N_9") (pintype "bidirectional"))
    )
    (net (code "69") (name "unconnected-(U7-IO36{slash}SEN_VP{slash}A1_0-Pad4)") (class "Default")
      (node (ref "U7") (pin "4") (pinfunction "IO36/SEN_VP/A1_0_4") (pintype "passive"))
    )
    (net (code "70") (name "unconnected-(U7-IO39{slash}SEN_VN{slash}A1_3-Pad5)") (class "Default")
      (node (ref "U7") (pin "5") (pinfunction "IO39/SEN_VN/A1_3_5") (pintype "passive"))
    )
    (net (code "71") (name "unconnected-(U7-SD0-Pad21)") (class "Default")
      (node (ref "U7") (pin "21") (pinfunction "SD0_21") (pintype "bidirectional"))
    )
    (net (code "72") (name "unconnected-(U7-SD1-Pad22)") (class "Default")
      (node (ref "U7") (pin "22") (pinfunction "SD1_22") (pintype "bidirectional"))
    )
    (net (code "73") (name "unconnected-(U7-SD2-Pad17)") (class "Default")
      (node (ref "U7") (pin "17") (pinfunction "SD2_17") (pintype "bidirectional"))
    )
    (net (code "74") (name "unconnected-(U7-SD3-Pad18)") (class "Default")
      (node (ref "U7") (pin "18") (pinfunction "SD3_18") (pintype "bidirectional"))
    )
    (net (code "75") (name "unconnected-(USB1-ID-Pad4)") (class "Default")
      (node (ref "USB1") (pin "4") (pinfunction "ID_4") (pintype "bidirectional"))
    )
  )
)
